# DRIBLE.net
KiCad netlist of a schematic drawn in Altium Designer
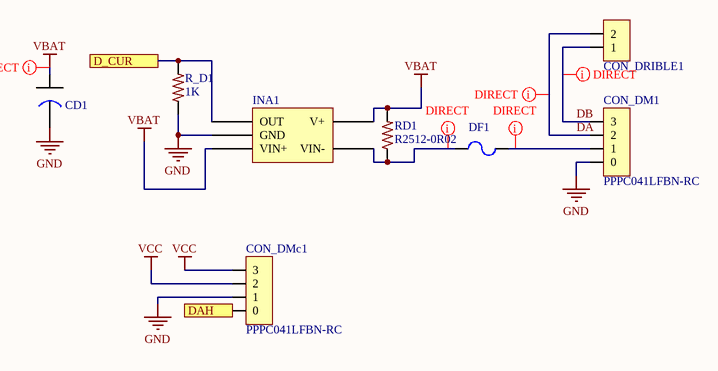
[diagram p0: DRIBLE.SchDoc]

(export (version "E")
  (design (tool "Eeschema 10.0.6"))
  (components
    (comp (ref "CD1")
      (value "EEE-FK1C681GP")
      (footprint "EEE-FK1C681GP")
      (description "Aluminum Electrolytic Capacitors - SMD Al Lytic Cap SMT FK Series 105C")
      (libsource (lib "Schlib1") (part "CAP AL 680UF/16V"))
    )
    (comp (ref "CON_DM1")
      (value "PPPC041LFBN-RC")
      (footprint "04x01_Conector_Female - duplicate")
      (description "4 Position Header Connector 0.100\" (2.54mm) Through Hole Gold")
      (libsource (lib "Schlib1") (part "04x01_Conector_Female-SCH"))
    )
    (comp (ref "CON_DMc1")
      (value "PPPC041LFBN-RC")
      (footprint "04x01_Conector_Female - duplicate")
      (description "4 Position Header Connector 0.100\" (2.54mm) Through Hole Gold")
      (libsource (lib "Schlib1") (part "04x01_Conector_Female-SCH"))
    )
    (comp (ref "CON_DRIBLE1")
      (value "0022112022")
      (footprint "02x01_Conector_Male")
      (description "CONN HEADER 2POS .100 VERT GOLD")
      (libsource (lib "Schlib1") (part "02x01_Conector_Male"))
    )
    (comp (ref "DF1")
      (value "MF-MSMF250/16X")
      (footprint "RESC4632X16N")
      (description "PTC RESETTABLE .30A 30V 1812")
      (libsource (lib "IMBEL") (part "MF-MSMF250/16X-01.A.1"))
    )
    (comp (ref "INA1")
      (value "INA169NA")
      (footprint "SOT95P280X125-5N")
      (description "IC CURRENT MONITOR 0.5% SOT23-5")
      (libsource (lib "IMBEL") (part "ina169"))
    )
    (comp (ref "RD1")
      (value "R2512-0R02")
      (footprint "2512-RES-HD")
      (description "RES .02 OHM 2W 1% 2512 SMD")
      (fields (field (name "PART NO") "WSL2512R0200FEA18"))
      (libsource (lib "IMBEL") (part "R2512-0R02-4"))
    )
    (comp (ref "R_D1")
      (value "1K")
      (footprint "0402-RES-HD")
      (description "RES 1K OHM 1/10W 1% 0402 SMD")
      (fields (field (name "PART NO") "ERJ-2RKF1001X"))
      (libsource (lib "IMBEL") (part "RESISTOR"))
    )
  )
  (nets
    (net (code "1") (name "/DA") (class "Default")
      (node (ref "CON_DM1") (pin "2") (pinfunction "2_2") (pintype "passive"))
      (node (ref "CON_DRIBLE1") (pin "2") (pinfunction "2_2") (pintype "passive"))
    )
    (net (code "2") (name "/DAH") (class "Default")
      (node (ref "CON_DMc1") (pin "0") (pinfunction "0_0") (pintype "passive"))
    )
    (net (code "3") (name "/DB") (class "Default")
      (node (ref "CON_DM1") (pin "3") (pinfunction "3_3") (pintype "passive"))
      (node (ref "CON_DRIBLE1") (pin "1") (pinfunction "1_1") (pintype "passive"))
    )
    (net (code "4") (name "/D_CUR") (class "Default")
      (node (ref "INA1") (pin "1") (pinfunction "OUT_1") (pintype "passive"))
      (node (ref "R_D1") (pin "2") (pinfunction "2_2") (pintype "passive"))
    )
    (net (code "5") (name "GND") (class "Default")
      (node (ref "CD1") (pin "2") (pinfunction "2_2") (pintype "passive"))
      (node (ref "CON_DM1") (pin "0") (pinfunction "0_0") (pintype "passive"))
      (node (ref "CON_DMc1") (pin "1") (pinfunction "1_1") (pintype "passive"))
      (node (ref "INA1") (pin "2") (pinfunction "GND_2") (pintype "passive"))
      (node (ref "R_D1") (pin "1") (pinfunction "1_1") (pintype "passive"))
    )
    (net (code "6") (name "Net-(CON_DM1-Pad1)") (class "Default")
      (node (ref "CON_DM1") (pin "1") (pinfunction "1_1") (pintype "passive"))
      (node (ref "DF1") (pin "1") (pinfunction "1_1") (pintype "passive"))
    )
    (net (code "7") (name "Net-(INA1-VIN-)") (class "Default")
      (node (ref "DF1") (pin "2") (pinfunction "2_2") (pintype "passive"))
      (node (ref "INA1") (pin "5") (pinfunction "VIN-_5") (pintype "passive"))
      (node (ref "RD1") (pin "1") (pinfunction "1_1") (pintype "passive"))
    )
    (net (code "8") (name "VBAT") (class "Default")
      (node (ref "CD1") (pin "1") (pinfunction "1_1") (pintype "passive"))
      (node (ref "INA1") (pin "3") (pinfunction "VIN+_3") (pintype "passive"))
      (node (ref "INA1") (pin "4") (pinfunction "V+_4") (pintype "passive"))
      (node (ref "RD1") (pin "2") (pinfunction "2_2") (pintype "passive"))
    )
    (net (code "9") (name "VCC") (class "Default")
      (node (ref "CON_DMc1") (pin "2") (pinfunction "2_2") (pintype "passive"))
      (node (ref "CON_DMc1") (pin "3") (pinfunction "3_3") (pintype "passive"))
    )
  )
)
